# MCU_A.net
KiCad netlist of a schematic drawn in Altium Designer
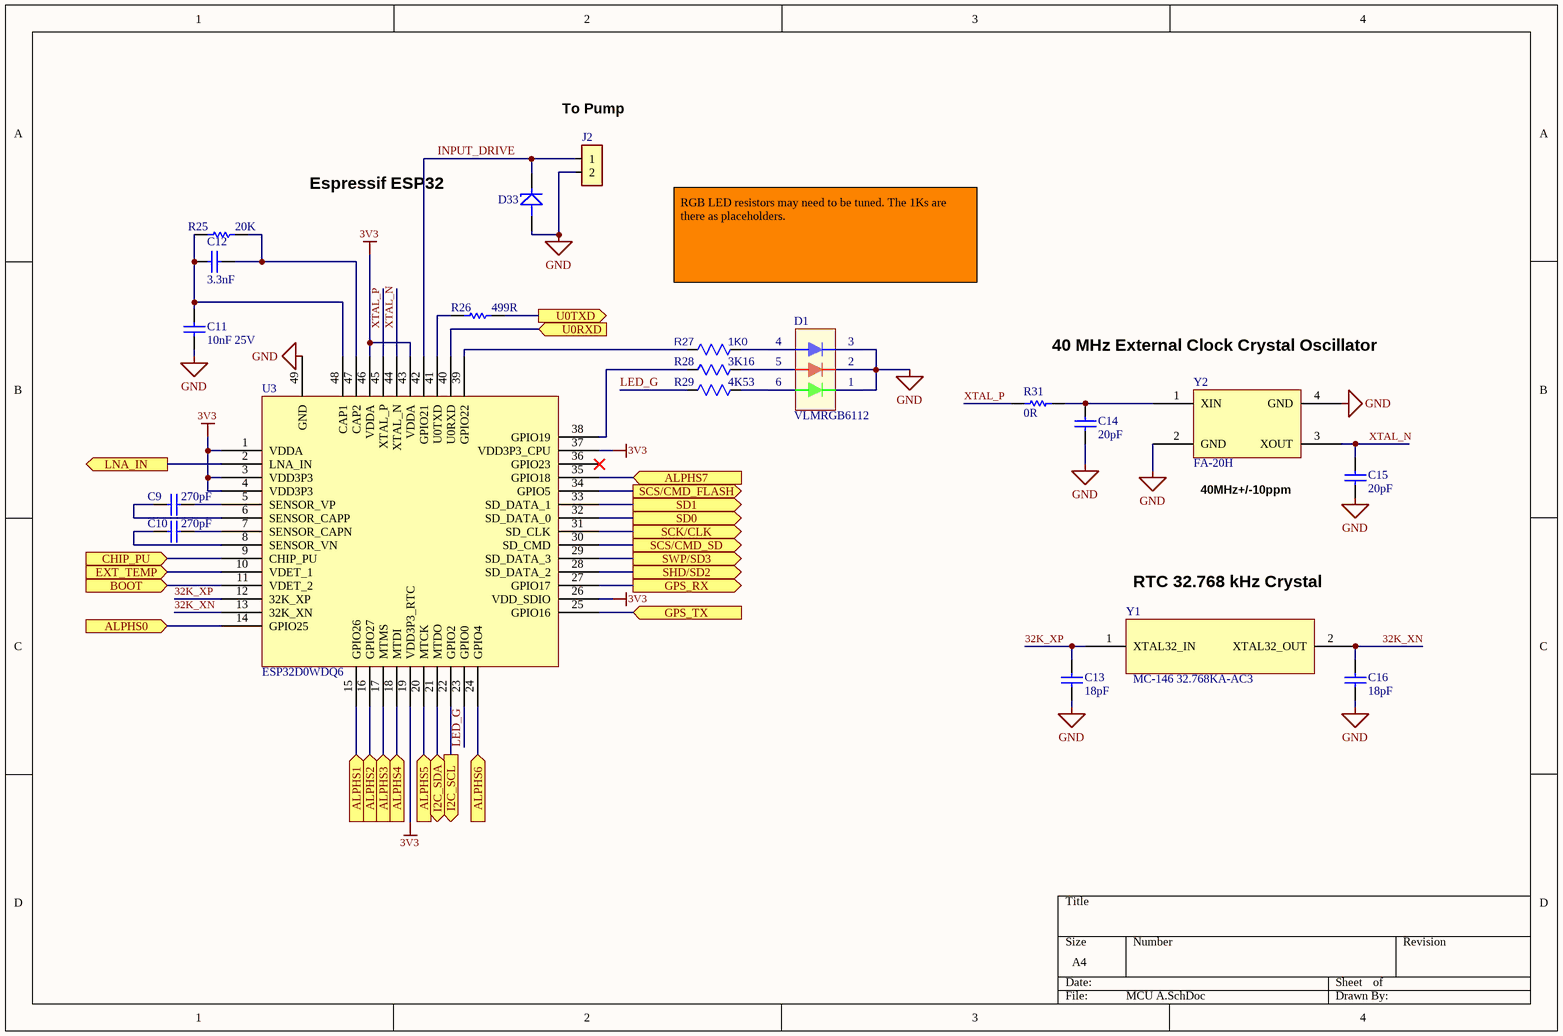
[diagram p0: MCU A.SchDoc]

(export (version "E")
  (design (tool "Eeschema 10.0.6"))
  (components
    (comp (ref "C9")
      (value "270pF")
      (footprint "C1005[0402]")
      (description "Cap,270pF,50V,10%,X7R,0402")
      (fields
        (field (name "MANUFACTURER PART NUMBER") "CL05B271KB5NNNC")
        (field (name "MANUFACTURER") "Samsung Electro-Mechanics")
      )
      (libsource (lib "Capacitors") (part "270pF_0402_50V"))
    )
    (comp (ref "C10")
      (value "270pF")
      (footprint "C1005[0402]")
      (description "Cap,270pF,50V,10%,X7R,0402")
      (fields
        (field (name "MANUFACTURER PART NUMBER") "CL05B271KB5NNNC")
        (field (name "MANUFACTURER") "Samsung Electro-Mechanics")
      )
      (libsource (lib "Capacitors") (part "270pF_0402_50V"))
    )
    (comp (ref "C11")
      (value "10nF 25V")
      (footprint "C1005[0402]")
      (description "Cap,SMD,10nF,25V,10%,X7R,0402")
      (fields
        (field (name "MANUFACTURER PART NUMBER") "CL05B103KA5NNNC")
        (field (name "MANUFACTURER") "Samsung Electro-Mechanics")
      )
      (libsource (lib "Capacitors") (part "10nF_0402_25V"))
    )
    (comp (ref "C12")
      (value "3.3nF")
      (footprint "C1005[0402]")
      (description "Cap,3.3nF,16V,10%,X7R,0402")
      (fields
        (field (name "MANUFACTURER PART NUMBER") "CC0402KRX7R7BB332")
        (field (name "MANUFACTURER") "Yageo")
      )
      (libsource (lib "Capacitors") (part "3.3nF_0402_16V"))
    )
    (comp (ref "C13")
      (value "18pF")
      (footprint "C1005[0402]")
      (description "Cap,18pF,50V,5%,C0G/NP0,0402")
      (fields
        (field (name "MANUFACTURER PART NUMBER") "CC0402JRNPO9BN180")
        (field (name "MANUFACTURER") "Yageo")
      )
      (libsource (lib "Capacitors") (part "18pF_0402_50V"))
    )
    (comp (ref "C14")
      (value "20pF")
      (footprint "C1005[0402]")
      (description "Cap,20pF,50V,5%,C0G/NP0,0402")
      (fields
        (field (name "MANUFACTURER PART NUMBER") "CC0402JRNPO9BN200")
        (field (name "MANUFACTURER") "Yageo")
      )
      (libsource (lib "Capacitors") (part "20pF_0402_50V"))
    )
    (comp (ref "C15")
      (value "20pF")
      (footprint "C1005[0402]")
      (description "Cap,20pF,50V,5%,C0G/NP0,0402")
      (fields
        (field (name "MANUFACTURER PART NUMBER") "CC0402JRNPO9BN200")
        (field (name "MANUFACTURER") "Yageo")
      )
      (libsource (lib "Capacitors") (part "20pF_0402_50V"))
    )
    (comp (ref "C16")
      (value "18pF")
      (footprint "C1005[0402]")
      (description "Cap,18pF,50V,5%,C0G/NP0,0402")
      (fields
        (field (name "MANUFACTURER PART NUMBER") "CC0402JRNPO9BN180")
        (field (name "MANUFACTURER") "Yageo")
      )
      (libsource (lib "Capacitors") (part "18pF_0402_50V"))
    )
    (comp (ref "D1")
      (value "VLMRGB6112")
      (footprint "VLMRGB6112")
      (description "LED RGB Clear 624nm/526nm/469nm 2V/3.1V/3V PLCC-6")
      (fields
        (field (name "MANUFACTURER") "Vishay Semiconductor Opto Division")
        (field (name "MANUFACTURER PART NUMBER") "VLMRGB6112-00-GS08")
      )
      (libsource (lib "LEDs") (part "VLMRGB6112"))
    )
    (comp (ref "D33")
      (value "3.3V TVS")
      (footprint "NXP PTVSxS1UR-Series (SOD123W)")
      (fields
        (field (name "MANUFACTURER") "Nexperia")
        (field (name "MANUFACTURER PART NUMBER") "PTVS3V3S1UTR,115")
      )
      (libsource (lib "FSM_2018") (part "NXP PTVSxS1UR-Series"))
    )
    (comp (ref "J2")
      (value "To Pump")
      (footprint "6410/2pin")
      (description "Connector 2 pin")
      (fields (field (name "MANUFACTURER") "Molex") (field (name "MANUFACTURER PART NUMBER") "0022232023"))
      (libsource (lib "VolcDB") (part "CON2"))
    )
    (comp (ref "R25")
      (value "20K")
      (footprint "R1005[0402]")
      (description "Resistor")
      (fields
        (field (name "MANUFACTURER") "Panasonic")
        (field (name "MANUFACTURER PART NUMBER") "ERJ-2GEJ203X")
      )
      (libsource (lib "Miscellaneous Devices") (part "Res1"))
    )
    (comp (ref "R26")
      (value "499R")
      (footprint "RESC1005X03N")
      (description "Resistor")
      (fields
        (field (name "MANUFACTURER PART NUMBER") "ERJ-2RKF4990X")
        (field (name "MANUFACTURER") "Panasonic")
      )
      (libsource (lib "Miscellaneous Devices") (part "Res1"))
    )
    (comp (ref "R27")
      (value "1K0")
      (footprint "R1608[0603] small")
      (description "RES 1K Ohm ±5%, 0.25W,1/4W 0603")
      (fields (field (name "MANUFACTURER") "Rohm") (field (name "MANUFACTURER PART NUMBER") "ESR03EZPJ102"))
      (libsource (lib "Resistors") (part "1K00_0603_0.1W"))
    )
    (comp (ref "R28")
      (value "3K16")
      (footprint "R1608[0603] small")
      (description "Res,SMD,1/10W,3K16,0603,1%")
      (fields
        (field (name "MANUFACTURER") "Stackpole Electronics")
        (field (name "MANUFACTURER PART NUMBER") "RMCF0603FT3K16")
      )
      (libsource (lib "Resistors") (part "3K16_Resistor_0603"))
    )
    (comp (ref "R29")
      (value "4K53")
      (footprint "R1608[0603] small")
      (description "Res,SMD,4K53,1/10W,1%,0603")
      (fields
        (field (name "MANUFACTURER") "Yageo")
        (field (name "MANUFACTURER PART NUMBER") "RC0603FR-074K53L")
      )
      (libsource (lib "Resistors") (part "4K53_Resistor_0603"))
    )
    (comp (ref "R31")
      (value "0R")
      (footprint "RESC1005X03N")
      (description "Resistor")
      (fields
        (field (name "MANUFACTURER PART NUMBER") "ERJ-2GE0R00X")
        (field (name "MANUFACTURER") "Panasonic")
        (field (name "PUBLISHER") "Altium Limited")
      )
      (libsource (lib "Miscellaneous Devices") (part "Res1"))
    )
    (comp (ref "U3")
      (value "ESP32D0WDQ6")
      (footprint "QFN40P600X600X90_HS-49N")
      (description "Microcontroller")
      (fields
        (field (name "MANUFACTURER") "Espressif Systems")
        (field (name "MANUFACTURER PART NUMBER") "ESP32-D0WDQ6")
      )
      (libsource (lib "Gas Monitor Components") (part "ESP32"))
    )
    (comp (ref "Y1")
      (value "MC-146 32.768KA-AC3")
      (footprint "MC-146")
      (description "32.768 kHz Crystal")
      (fields
        (field (name "MANUFACTURER") "EPSON")
        (field (name "MANUFACTURER PART NUMBER") "MC-146 32.768KA-AC3:ROHS")
      )
      (libsource (lib "Gas Monitor Components") (part "MC-146 32.768KA-AC3"))
    )
    (comp (ref "Y2")
      (value "FA-20H")
      (footprint "FA-20H")
      (description "40MHz Crystal Oscillator")
      (fields
        (field (name "MANUFACTURER") "EPSON")
        (field (name "MANUFACTURER PART NUMBER") "FA-20H 40.0000MF10Z-K3")
      )
      (libsource (lib "Gas Monitor Components") (part "Y1"))
    )
  )
  (nets
    (net (code "1") (name "/32K_XN") (class "Default")
      (node (ref "C16") (pin "2") (pintype "passive"))
      (node (ref "U3") (pin "13") (pinfunction "32K_XN_13") (pintype "passive"))
      (node (ref "Y1") (pin "2") (pinfunction "XTAL32_OUT_2") (pintype "passive"))
    )
    (net (code "2") (name "/32K_XP") (class "Default")
      (node (ref "C13") (pin "2") (pintype "passive"))
      (node (ref "U3") (pin "12") (pinfunction "32K_XP_12") (pintype "passive"))
      (node (ref "Y1") (pin "1") (pinfunction "XTAL32_IN_1") (pintype "passive"))
    )
    (net (code "3") (name "/ALPHS0") (class "Default")
      (node (ref "U3") (pin "14") (pinfunction "GPIO25_14") (pintype "passive"))
    )
    (net (code "4") (name "/ALPHS1") (class "Default")
      (node (ref "U3") (pin "15") (pinfunction "GPIO26_15") (pintype "passive"))
    )
    (net (code "5") (name "/ALPHS2") (class "Default")
      (node (ref "U3") (pin "16") (pinfunction "GPIO27_16") (pintype "passive"))
    )
    (net (code "6") (name "/ALPHS3") (class "Default")
      (node (ref "U3") (pin "17") (pinfunction "MTMS_17") (pintype "passive"))
    )
    (net (code "7") (name "/ALPHS4") (class "Default")
      (node (ref "U3") (pin "18") (pinfunction "MTDI_18") (pintype "passive"))
    )
    (net (code "8") (name "/ALPHS5") (class "Default")
      (node (ref "U3") (pin "20") (pinfunction "MTCK_20") (pintype "passive"))
    )
    (net (code "9") (name "/ALPHS6") (class "Default")
      (node (ref "U3") (pin "24") (pinfunction "GPIO4_24") (pintype "passive"))
    )
    (net (code "10") (name "/ALPHS7") (class "Default")
      (node (ref "U3") (pin "35") (pinfunction "GPIO18_35") (pintype "passive"))
    )
    (net (code "11") (name "/BOOT") (class "Default")
      (node (ref "U3") (pin "11") (pinfunction "VDET_2_11") (pintype "passive"))
    )
    (net (code "12") (name "/CHIP_PU") (class "Default")
      (node (ref "U3") (pin "9") (pinfunction "CHIP_PU_9") (pintype "passive"))
    )
    (net (code "13") (name "/EXT_TEMP") (class "Default")
      (node (ref "U3") (pin "10") (pinfunction "VDET_1_10") (pintype "passive"))
    )
    (net (code "14") (name "/GPS_RX") (class "Default")
      (node (ref "U3") (pin "27") (pinfunction "GPIO17_27") (pintype "passive"))
    )
    (net (code "15") (name "/GPS_TX") (class "Default")
      (node (ref "U3") (pin "25") (pinfunction "GPIO16_25") (pintype "passive"))
    )
    (net (code "16") (name "/I2C_SCL") (class "Default")
      (node (ref "U3") (pin "22") (pinfunction "GPIO2_22") (pintype "passive"))
    )
    (net (code "17") (name "/I2C_SDA") (class "Default")
      (node (ref "U3") (pin "21") (pinfunction "MTDO_21") (pintype "passive"))
    )
    (net (code "18") (name "/INPUT_DRIVE") (class "Default")
      (node (ref "D33") (pin "1") (pinfunction "1_1") (pintype "passive"))
      (node (ref "J2") (pin "1") (pinfunction "1_1") (pintype "passive"))
      (node (ref "U3") (pin "42") (pinfunction "GPIO21_42") (pintype "passive"))
    )
    (net (code "19") (name "/LED_G") (class "Default")
      (node (ref "R29") (pin "1") (pintype "passive"))
      (node (ref "U3") (pin "23") (pinfunction "GPIO0_23") (pintype "passive"))
    )
    (net (code "20") (name "/LNA_IN") (class "Default")
      (node (ref "U3") (pin "2") (pinfunction "LNA_IN_2") (pintype "passive"))
    )
    (net (code "21") (name "/SCK{slash}CLK") (class "Default")
      (node (ref "U3") (pin "31") (pinfunction "SD_CLK_31") (pintype "passive"))
    )
    (net (code "22") (name "/SCS{slash}CMD_FLASH") (class "Default")
      (node (ref "U3") (pin "34") (pinfunction "GPIO5_34") (pintype "passive"))
    )
    (net (code "23") (name "/SCS{slash}CMD_SD") (class "Default")
      (node (ref "U3") (pin "30") (pinfunction "SD_CMD_30") (pintype "passive"))
    )
    (net (code "24") (name "/SD0") (class "Default")
      (node (ref "U3") (pin "32") (pinfunction "SD_DATA_0_32") (pintype "passive"))
    )
    (net (code "25") (name "/SD1") (class "Default")
      (node (ref "U3") (pin "33") (pinfunction "SD_DATA_1_33") (pintype "passive"))
    )
    (net (code "26") (name "/SHD{slash}SD2") (class "Default")
      (node (ref "U3") (pin "28") (pinfunction "SD_DATA_2_28") (pintype "passive"))
    )
    (net (code "27") (name "/SWP{slash}SD3") (class "Default")
      (node (ref "U3") (pin "29") (pinfunction "SD_DATA_3_29") (pintype "passive"))
    )
    (net (code "28") (name "/U0RXD") (class "Default")
      (node (ref "U3") (pin "40") (pinfunction "U0RXD_40") (pintype "passive"))
    )
    (net (code "29") (name "/U0TXD") (class "Default")
      (node (ref "R26") (pin "2") (pinfunction "2_2") (pintype "passive"))
    )
    (net (code "30") (name "/XTAL_N") (class "Default")
      (node (ref "C15") (pin "2") (pintype "passive"))
      (node (ref "U3") (pin "44") (pinfunction "XTAL_N_44") (pintype "passive"))
      (node (ref "Y2") (pin "3") (pinfunction "XOUT_3") (pintype "passive"))
    )
    (net (code "31") (name "/XTAL_P") (class "Default")
      (node (ref "R31") (pin "1") (pinfunction "1_1") (pintype "passive"))
      (node (ref "U3") (pin "45") (pinfunction "XTAL_P_45") (pintype "passive"))
    )
    (net (code "32") (name "3V3") (class "Default")
      (node (ref "U3") (pin "1") (pinfunction "VDDA_1") (pintype "power_in"))
      (node (ref "U3") (pin "19") (pinfunction "VDD3P3_RTC_19") (pintype "passive"))
      (node (ref "U3") (pin "26") (pinfunction "VDD_SDIO_26") (pintype "passive"))
      (node (ref "U3") (pin "3") (pinfunction "VDD3P3_3") (pintype "power_in"))
      (node (ref "U3") (pin "37") (pinfunction "VDD3P3_CPU_37") (pintype "passive"))
      (node (ref "U3") (pin "4") (pinfunction "VDD3P3_4") (pintype "passive"))
      (node (ref "U3") (pin "43") (pinfunction "VDDA_43") (pintype "power_in"))
      (node (ref "U3") (pin "46") (pinfunction "VDDA_46") (pintype "power_in"))
    )
    (net (code "33") (name "GND") (class "Default")
      (node (ref "C11") (pin "1") (pintype "passive"))
      (node (ref "C13") (pin "1") (pintype "passive"))
      (node (ref "C14") (pin "1") (pintype "passive"))
      (node (ref "C15") (pin "1") (pintype "passive"))
      (node (ref "C16") (pin "1") (pintype "passive"))
      (node (ref "D1") (pin "1") (pinfunction "A2_1") (pintype "passive"))
      (node (ref "D1") (pin "2") (pinfunction "C3_2") (pintype "passive"))
      (node (ref "D1") (pin "3") (pinfunction "A3_3") (pintype "passive"))
      (node (ref "D33") (pin "2") (pinfunction "2_2") (pintype "passive"))
      (node (ref "J2") (pin "2") (pinfunction "2_2") (pintype "passive"))
      (node (ref "U3") (pin "49") (pinfunction "GND_49") (pintype "power_in"))
      (node (ref "Y2") (pin "2") (pinfunction "GND_2") (pintype "power_in"))
      (node (ref "Y2") (pin "4") (pinfunction "GND_4") (pintype "power_in"))
    )
    (net (code "34") (name "Net-(D1-C1-Pad4)") (class "Default")
      (node (ref "D1") (pin "4") (pinfunction "C1_4") (pintype "passive"))
      (node (ref "R27") (pin "2") (pintype "passive"))
    )
    (net (code "35") (name "Net-(D1-C1-Pad5)") (class "Default")
      (node (ref "D1") (pin "5") (pinfunction "C1_5") (pintype "passive"))
      (node (ref "R28") (pin "2") (pintype "passive"))
    )
    (net (code "36") (name "Net-(D1-C1-Pad6)") (class "Default")
      (node (ref "D1") (pin "6") (pinfunction "C1_6") (pintype "passive"))
      (node (ref "R29") (pin "2") (pintype "passive"))
    )
    (net (code "37") (name "Net-(U3-CAP1)") (class "Default")
      (node (ref "C11") (pin "2") (pintype "passive"))
      (node (ref "C12") (pin "2") (pintype "passive"))
      (node (ref "R25") (pin "1") (pinfunction "1_1") (pintype "passive"))
      (node (ref "U3") (pin "48") (pinfunction "CAP1_48") (pintype "passive"))
    )
    (net (code "38") (name "Net-(U3-CAP2)") (class "Default")
      (node (ref "C12") (pin "1") (pintype "passive"))
      (node (ref "R25") (pin "2") (pinfunction "2_2") (pintype "passive"))
      (node (ref "U3") (pin "47") (pinfunction "CAP2_47") (pintype "passive"))
    )
    (net (code "39") (name "Net-(U3-GPIO19)") (class "Default")
      (node (ref "R28") (pin "1") (pintype "passive"))
      (node (ref "U3") (pin "38") (pinfunction "GPIO19_38") (pintype "passive"))
    )
    (net (code "40") (name "Net-(U3-GPIO22)") (class "Default")
      (node (ref "R27") (pin "1") (pintype "passive"))
      (node (ref "U3") (pin "39") (pinfunction "GPIO22_39") (pintype "passive"))
    )
    (net (code "41") (name "Net-(U3-SENSOR_CAPN)") (class "Default")
      (node (ref "C10") (pin "1") (pintype "passive"))
      (node (ref "U3") (pin "7") (pinfunction "SENSOR_CAPN_7") (pintype "passive"))
    )
    (net (code "42") (name "Net-(U3-SENSOR_CAPP)") (class "Default")
      (node (ref "C9") (pin "2") (pintype "passive"))
      (node (ref "U3") (pin "6") (pinfunction "SENSOR_CAPP_6") (pintype "passive"))
    )
    (net (code "43") (name "Net-(U3-SENSOR_VN)") (class "Default")
      (node (ref "C10") (pin "2") (pintype "passive"))
      (node (ref "U3") (pin "8") (pinfunction "SENSOR_VN_8") (pintype "passive"))
    )
    (net (code "44") (name "Net-(U3-SENSOR_VP)") (class "Default")
      (node (ref "C9") (pin "1") (pintype "passive"))
      (node (ref "U3") (pin "5") (pinfunction "SENSOR_VP_5") (pintype "passive"))
    )
    (net (code "45") (name "Net-(U3-U0TXD)") (class "Default")
      (node (ref "R26") (pin "1") (pinfunction "1_1") (pintype "passive"))
      (node (ref "U3") (pin "41") (pinfunction "U0TXD_41") (pintype "passive"))
    )
    (net (code "46") (name "Net-(Y2-XIN)") (class "Default")
      (node (ref "C14") (pin "2") (pintype "passive"))
      (node (ref "R31") (pin "2") (pinfunction "2_2") (pintype "passive"))
      (node (ref "Y2") (pin "1") (pinfunction "XIN_1") (pintype "passive"))
    )
    (net (code "47") (name "unconnected-(U3-GPIO23-Pad36)") (class "Default")
      (node (ref "U3") (pin "36") (pinfunction "GPIO23_36") (pintype "passive+no_connect"))
    )
  )
)
